# adc_dac_txquad6.net
KiCad netlist of a schematic drawn in Altium Designer
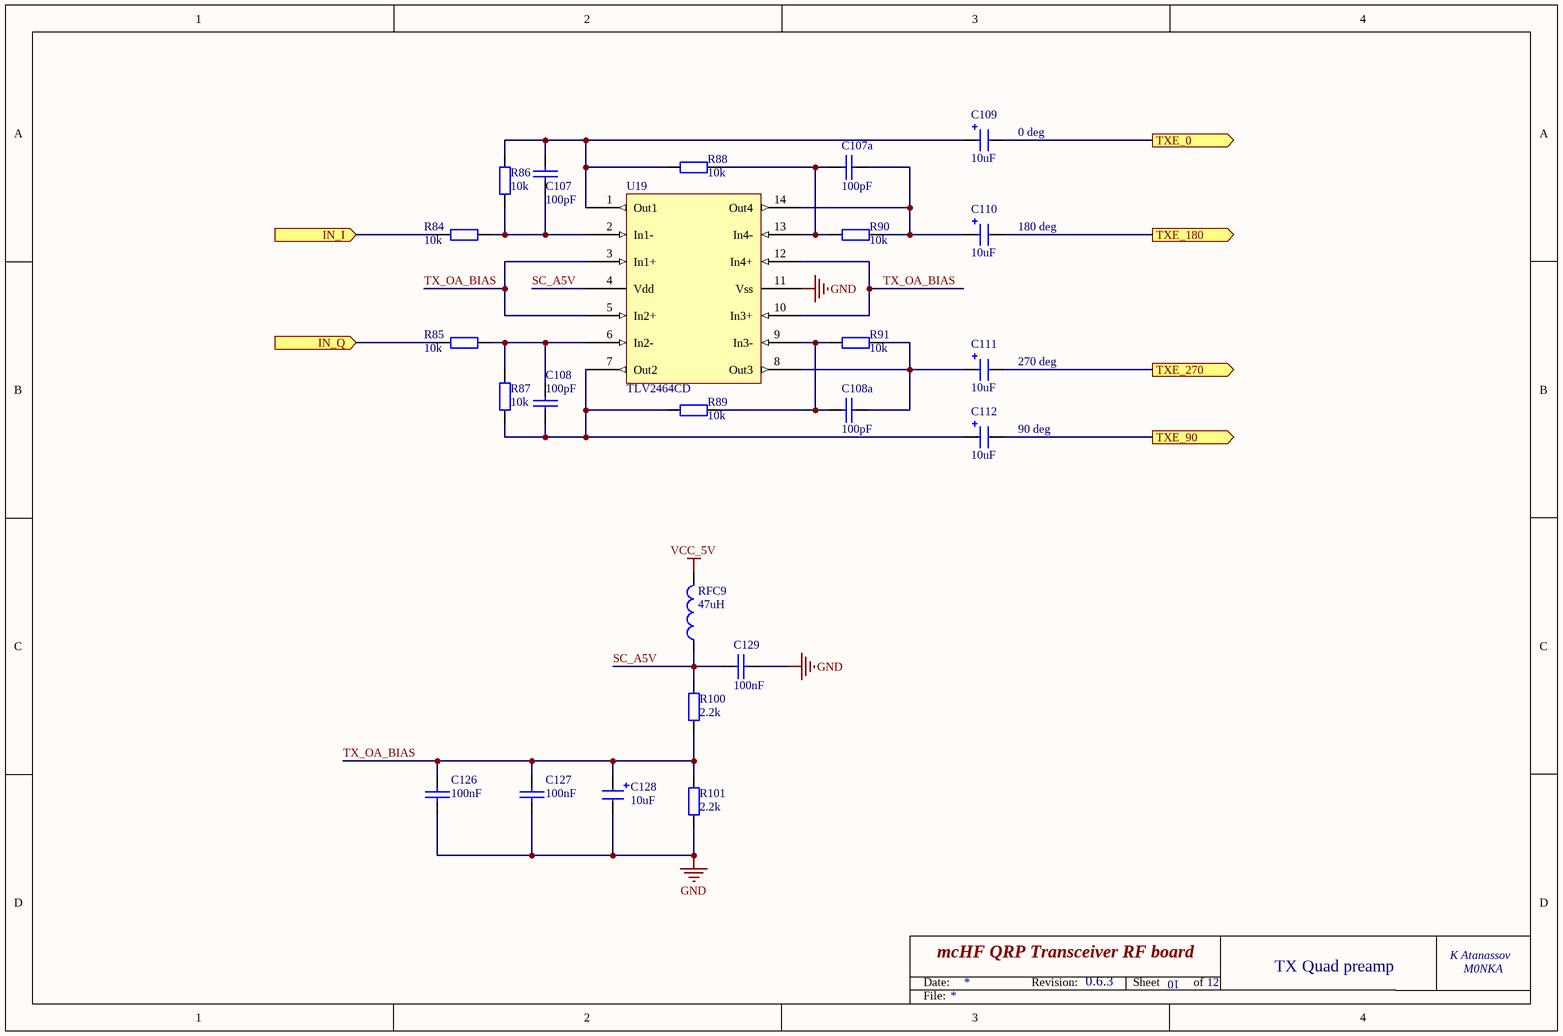
[diagram p0: adc_dac_txquad6.SchDoc]

(export (version "E")
  (design (tool "Eeschema 10.0.6"))
  (components
    (comp (ref "C107")
      (value "100pF")
      (footprint "0805-Pro")
      (description "Capacitor")
      (libsource (lib "mcHF_rf") (part "CAP"))
    )
    (comp (ref "C107a")
      (value "100pF")
      (footprint "0805-Pro")
      (description "Capacitor")
      (libsource (lib "mcHF_rf") (part "CAP"))
    )
    (comp (ref "C108")
      (value "100pF")
      (footprint "0805-Pro")
      (description "Capacitor")
      (libsource (lib "mcHF_rf") (part "CAP"))
    )
    (comp (ref "C108a")
      (value "100pF")
      (footprint "0805-Pro")
      (description "Capacitor")
      (libsource (lib "mcHF_rf") (part "CAP"))
    )
    (comp (ref "C109")
      (value "10uF")
      (footprint "1206_Elec_Cap_N")
      (description "Electrolitic capacitor")
      (libsource (lib "mcHF_rf") (part "CAP-POL"))
    )
    (comp (ref "C110")
      (value "10uF")
      (footprint "1206_Elec_Cap_N")
      (description "Electrolitic capacitor")
      (libsource (lib "mcHF_rf") (part "CAP-POL"))
    )
    (comp (ref "C111")
      (value "10uF")
      (footprint "1206_Elec_Cap_N")
      (description "Electrolitic capacitor")
      (libsource (lib "mcHF_rf") (part "CAP-POL"))
    )
    (comp (ref "C112")
      (value "10uF")
      (footprint "1206_Elec_Cap_N")
      (description "Electrolitic capacitor")
      (libsource (lib "mcHF_rf") (part "CAP-POL"))
    )
    (comp (ref "C126")
      (value "100nF")
      (footprint "0805-Pro")
      (description "Capacitor")
      (libsource (lib "mcHF_rf") (part "CAP"))
    )
    (comp (ref "C127")
      (value "100nF")
      (footprint "0805-Pro")
      (description "Capacitor")
      (libsource (lib "mcHF_rf") (part "CAP"))
    )
    (comp (ref "C128")
      (value "10uF")
      (footprint "1206_Elec_Cap_N")
      (description "Electrolitic capacitor")
      (libsource (lib "mcHF_rf") (part "CAP-POL"))
    )
    (comp (ref "C129")
      (value "100nF")
      (footprint "0805-Pro")
      (description "Capacitor")
      (libsource (lib "mcHF_rf") (part "CAP"))
    )
    (comp (ref "R84")
      (value "10k")
      (footprint "0805-Pro")
      (description "Resistor")
      (libsource (lib "") (part "RES_1"))
    )
    (comp (ref "R85")
      (value "10k")
      (footprint "0805-Pro")
      (description "Resistor")
      (libsource (lib "") (part "RES_1"))
    )
    (comp (ref "R86")
      (value "10k")
      (footprint "0805-Pro")
      (description "Resistor")
      (libsource (lib "mcHF_rf") (part "RES"))
    )
    (comp (ref "R87")
      (value "10k")
      (footprint "0805-Pro")
      (description "Resistor")
      (libsource (lib "mcHF_rf") (part "RES"))
    )
    (comp (ref "R88")
      (value "10k")
      (footprint "0805-Pro")
      (description "Resistor")
      (libsource (lib "") (part "RES_1"))
    )
    (comp (ref "R89")
      (value "10k")
      (footprint "0805-Pro")
      (description "Resistor")
      (libsource (lib "") (part "RES_1"))
    )
    (comp (ref "R90")
      (value "10k")
      (footprint "0805-Pro")
      (description "Resistor")
      (libsource (lib "") (part "RES_1"))
    )
    (comp (ref "R91")
      (value "10k")
      (footprint "0805-Pro")
      (description "Resistor")
      (libsource (lib "") (part "RES_1"))
    )
    (comp (ref "R100")
      (value "2.2k")
      (footprint "0805-Pro")
      (description "Resistor")
      (libsource (lib "mcHF_rf") (part "RES"))
    )
    (comp (ref "R101")
      (value "2.2k")
      (footprint "0805-Pro")
      (description "Resistor")
      (libsource (lib "mcHF_rf") (part "RES"))
    )
    (comp (ref "RFC9")
      (value "47uH")
      (footprint "0805-Pro")
      (description "INDUCTOR, SIGNAL LINE, 4.7UH, 1005")
      (libsource (lib "mcHF_rf") (part "TDK-NLV25T"))
    )
    (comp (ref "U19")
      (value "TLV2464CD")
      (footprint "SO-14-Pro")
      (description "Low Power, Rail-To-Rail OpAmp")
      (libsource (lib "mcHF_rf") (part "TLV2464CD"))
    )
  )
  (nets
    (net (code "1") (name "/IN_I") (class "Default")
      (node (ref "R84") (pin "1") (pinfunction "1_1") (pintype "passive"))
    )
    (net (code "2") (name "/IN_Q") (class "Default")
      (node (ref "R85") (pin "1") (pinfunction "1_1") (pintype "passive"))
    )
    (net (code "3") (name "/SC_A5V") (class "Default")
      (node (ref "C129") (pin "2") (pinfunction "2_2") (pintype "passive"))
      (node (ref "R100") (pin "2") (pinfunction "2_2") (pintype "passive"))
      (node (ref "RFC9") (pin "1") (pinfunction "1_1") (pintype "passive"))
      (node (ref "U19") (pin "4") (pinfunction "Vdd_4") (pintype "power_in"))
    )
    (net (code "4") (name "/TXE_0") (class "Default")
      (node (ref "C109") (pin "2") (pinfunction "2_2") (pintype "passive"))
    )
    (net (code "5") (name "/TXE_90") (class "Default")
      (node (ref "C112") (pin "2") (pinfunction "2_2") (pintype "passive"))
    )
    (net (code "6") (name "/TXE_180") (class "Default")
      (node (ref "C110") (pin "2") (pinfunction "2_2") (pintype "passive"))
    )
    (net (code "7") (name "/TXE_270") (class "Default")
      (node (ref "C111") (pin "2") (pinfunction "2_2") (pintype "passive"))
    )
    (net (code "8") (name "/TX_OA_BIAS") (class "Default")
      (node (ref "C126") (pin "2") (pinfunction "2_2") (pintype "passive"))
      (node (ref "C127") (pin "2") (pinfunction "2_2") (pintype "passive"))
      (node (ref "C128") (pin "1") (pinfunction "1_1") (pintype "passive"))
      (node (ref "R100") (pin "1") (pinfunction "1_1") (pintype "passive"))
      (node (ref "R101") (pin "2") (pinfunction "2_2") (pintype "passive"))
      (node (ref "U19") (pin "10") (pinfunction "In3+_10") (pintype "input"))
      (node (ref "U19") (pin "12") (pinfunction "In4+_12") (pintype "input"))
      (node (ref "U19") (pin "3") (pinfunction "In1+_3") (pintype "input"))
      (node (ref "U19") (pin "5") (pinfunction "In2+_5") (pintype "input"))
    )
    (net (code "9") (name "GND") (class "Default")
      (node (ref "C126") (pin "1") (pinfunction "1_1") (pintype "passive"))
      (node (ref "C127") (pin "1") (pinfunction "1_1") (pintype "passive"))
      (node (ref "C128") (pin "2") (pinfunction "2_2") (pintype "passive"))
      (node (ref "C129") (pin "1") (pinfunction "1_1") (pintype "passive"))
      (node (ref "R101") (pin "1") (pinfunction "1_1") (pintype "passive"))
      (node (ref "U19") (pin "11") (pinfunction "Vss_11") (pintype "power_in"))
    )
    (net (code "10") (name "Net-(U19-In1-)") (class "Default")
      (node (ref "C107") (pin "1") (pinfunction "1_1") (pintype "passive"))
      (node (ref "R84") (pin "2") (pinfunction "2_2") (pintype "passive"))
      (node (ref "R86") (pin "1") (pinfunction "1_1") (pintype "passive"))
      (node (ref "U19") (pin "2") (pinfunction "In1-_2") (pintype "input"))
    )
    (net (code "11") (name "Net-(U19-In2-)") (class "Default")
      (node (ref "C108") (pin "2") (pinfunction "2_2") (pintype "passive"))
      (node (ref "R85") (pin "2") (pinfunction "2_2") (pintype "passive"))
      (node (ref "R87") (pin "2") (pinfunction "2_2") (pintype "passive"))
      (node (ref "U19") (pin "6") (pinfunction "In2-_6") (pintype "input"))
    )
    (net (code "12") (name "Net-(U19-In3-)") (class "Default")
      (node (ref "C108a") (pin "2") (pinfunction "2_2") (pintype "passive"))
      (node (ref "R89") (pin "2") (pinfunction "2_2") (pintype "passive"))
      (node (ref "R91") (pin "1") (pinfunction "1_1") (pintype "passive"))
      (node (ref "U19") (pin "9") (pinfunction "In3-_9") (pintype "input"))
    )
    (net (code "13") (name "Net-(U19-In4-)") (class "Default")
      (node (ref "C107a") (pin "2") (pinfunction "2_2") (pintype "passive"))
      (node (ref "R88") (pin "2") (pinfunction "2_2") (pintype "passive"))
      (node (ref "R90") (pin "1") (pinfunction "1_1") (pintype "passive"))
      (node (ref "U19") (pin "13") (pinfunction "In4-_13") (pintype "input"))
    )
    (net (code "14") (name "Net-(U19-Out1)") (class "Default")
      (node (ref "C107") (pin "2") (pinfunction "2_2") (pintype "passive"))
      (node (ref "C109") (pin "1") (pinfunction "1_1") (pintype "passive"))
      (node (ref "R86") (pin "2") (pinfunction "2_2") (pintype "passive"))
      (node (ref "R88") (pin "1") (pinfunction "1_1") (pintype "passive"))
      (node (ref "U19") (pin "1") (pinfunction "Out1_1") (pintype "output"))
    )
    (net (code "15") (name "Net-(U19-Out2)") (class "Default")
      (node (ref "C108") (pin "1") (pinfunction "1_1") (pintype "passive"))
      (node (ref "C112") (pin "1") (pinfunction "1_1") (pintype "passive"))
      (node (ref "R87") (pin "1") (pinfunction "1_1") (pintype "passive"))
      (node (ref "R89") (pin "1") (pinfunction "1_1") (pintype "passive"))
      (node (ref "U19") (pin "7") (pinfunction "Out2_7") (pintype "output"))
    )
    (net (code "16") (name "Net-(U19-Out3)") (class "Default")
      (node (ref "C108a") (pin "1") (pinfunction "1_1") (pintype "passive"))
      (node (ref "C111") (pin "1") (pinfunction "1_1") (pintype "passive"))
      (node (ref "R91") (pin "2") (pinfunction "2_2") (pintype "passive"))
      (node (ref "U19") (pin "8") (pinfunction "Out3_8") (pintype "output"))
    )
    (net (code "17") (name "Net-(U19-Out4)") (class "Default")
      (node (ref "C107a") (pin "1") (pinfunction "1_1") (pintype "passive"))
      (node (ref "C110") (pin "1") (pinfunction "1_1") (pintype "passive"))
      (node (ref "R90") (pin "2") (pinfunction "2_2") (pintype "passive"))
      (node (ref "U19") (pin "14") (pinfunction "Out4_14") (pintype "output"))
    )
    (net (code "18") (name "VCC_5V") (class "Default")
      (node (ref "RFC9") (pin "2") (pinfunction "2_2") (pintype "passive"))
    )
  )
)
